# schematic.net
KiCad netlist of a schematic drawn in EasyEDA
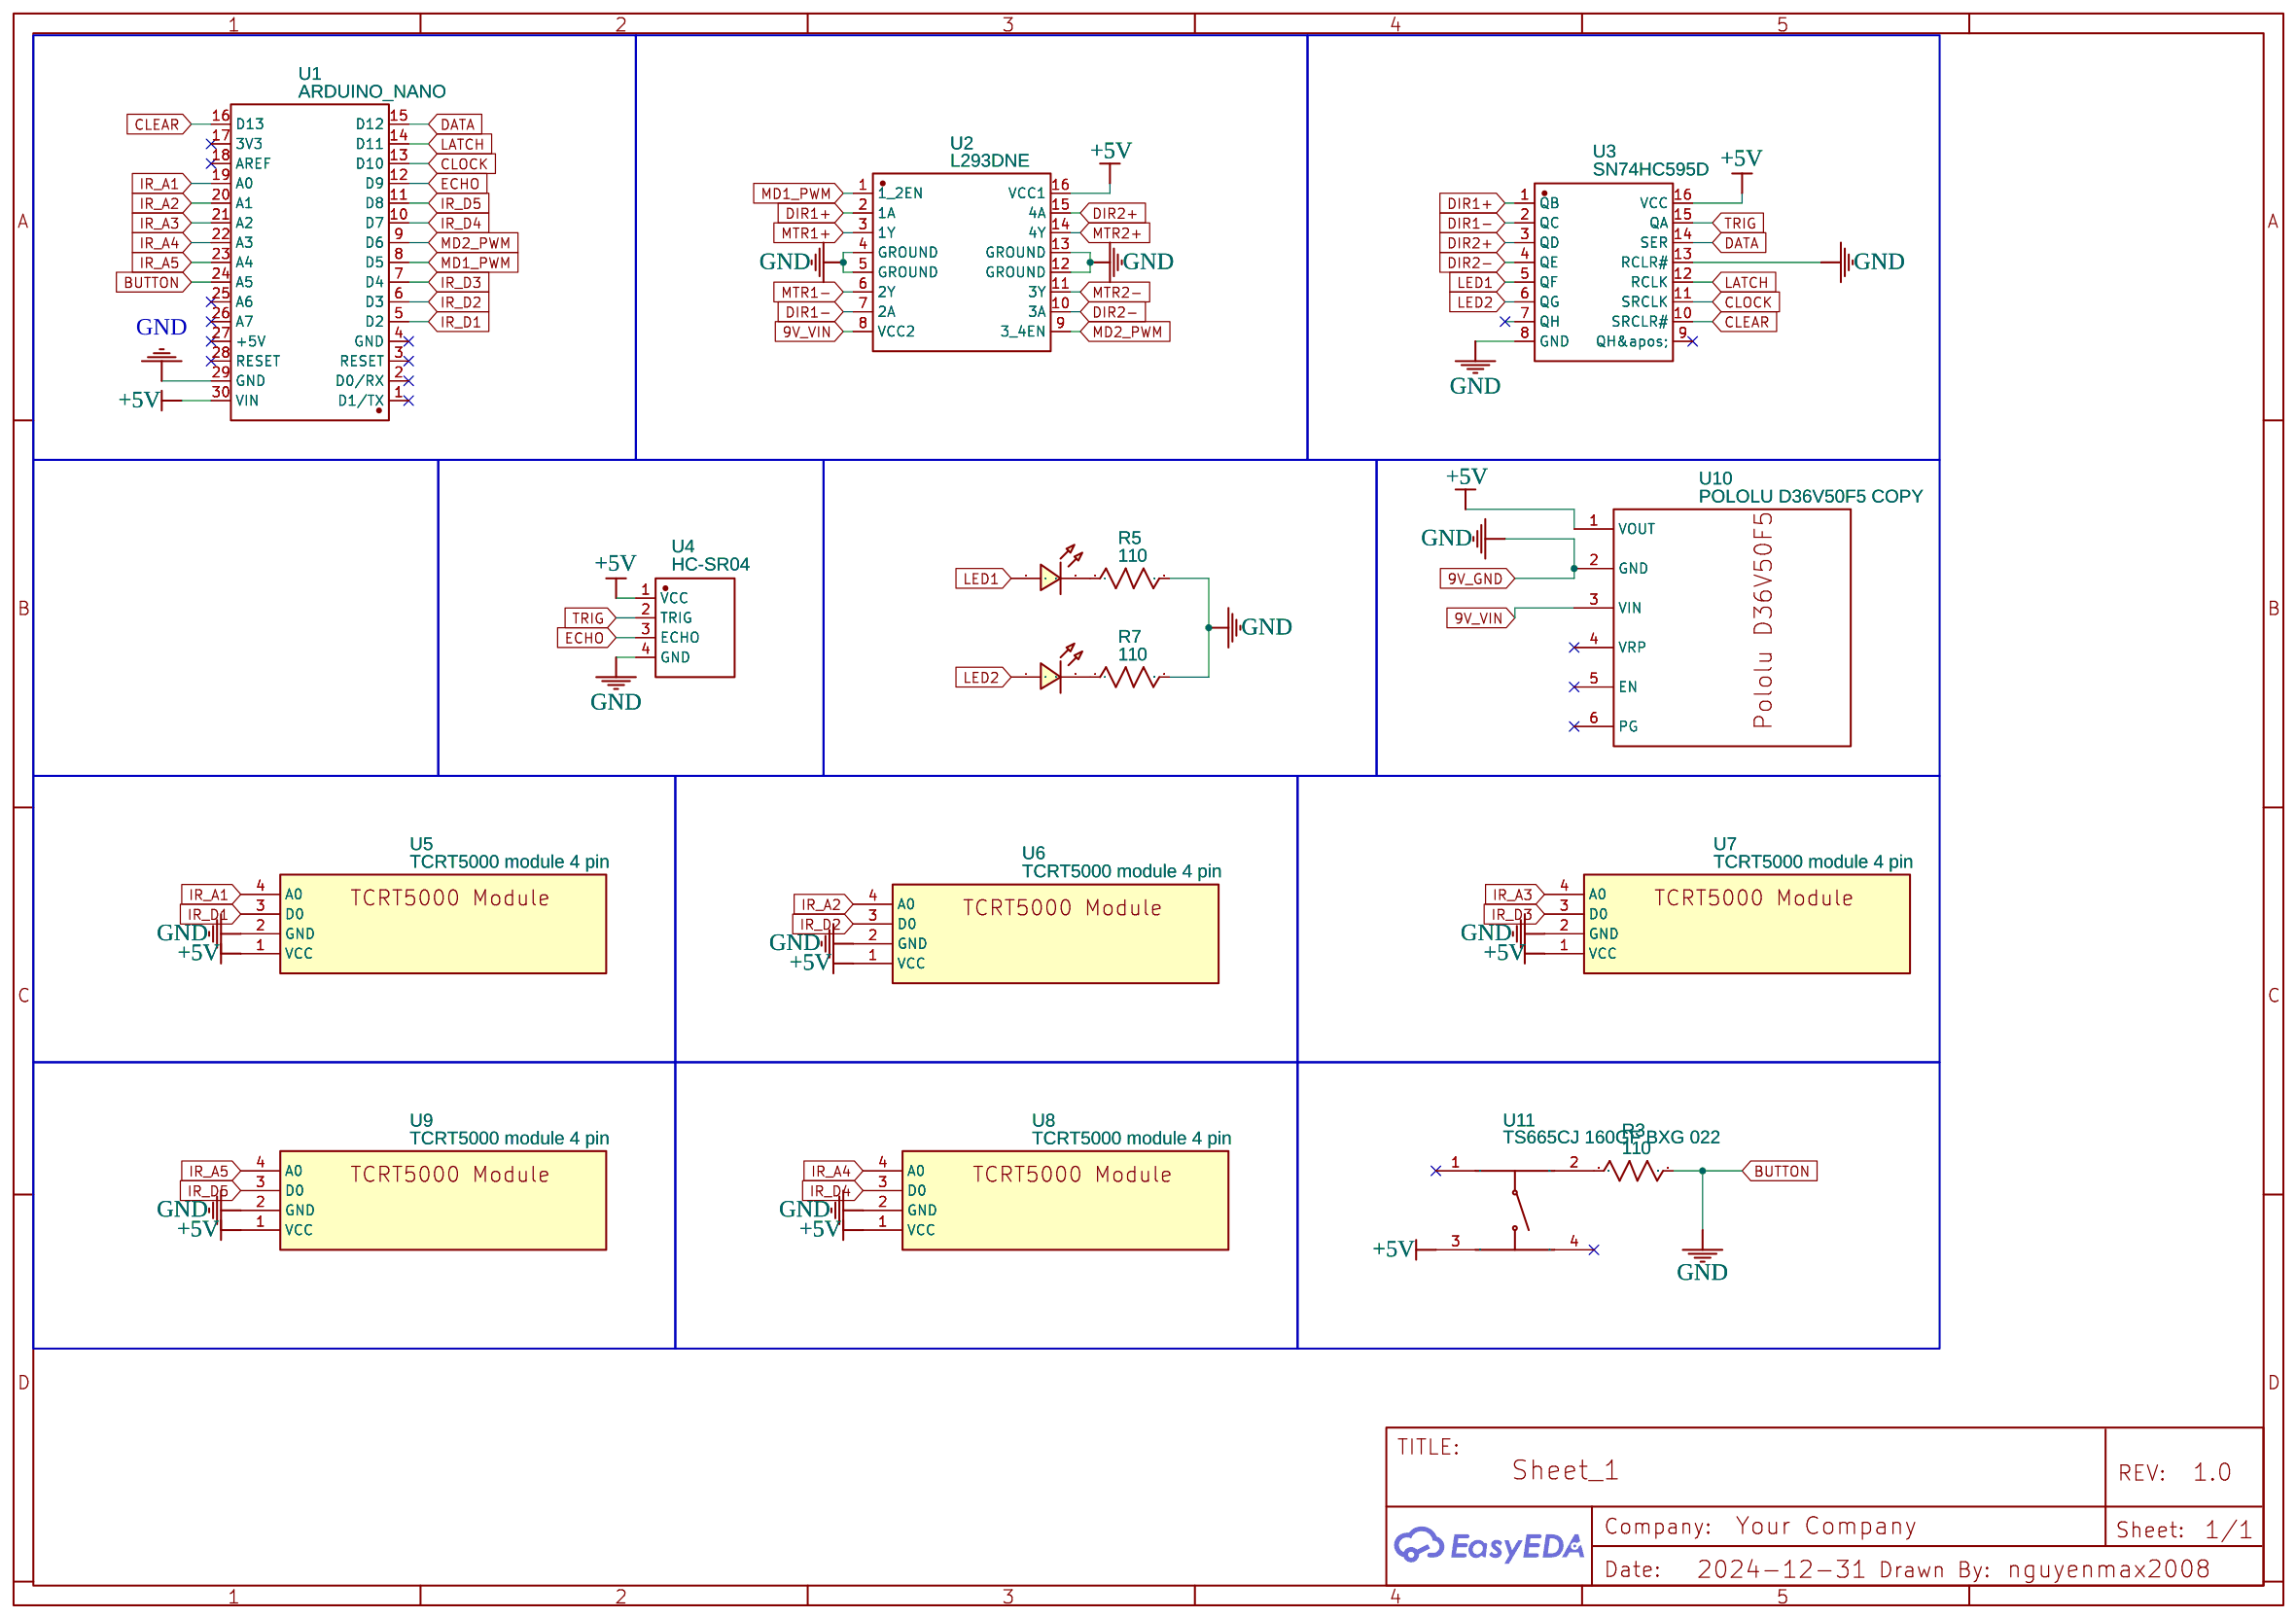
[diagram p0: schematic sheet]

(export (version "E")
  (design (tool "Eeschema 10.0.6"))
  (components
    (comp (ref "LED6")
      (value "LED-TH-3mm_R")
      (fields
        (field (name "Manufacturer Part") "204-10SDRD/S530-A3-L")
        (field (name "Manufacturer") "EVERLIGHT(台湾亿光)")
      )
      (libsource (lib "") (part "LED-TH-3mm_R"))
    )
    (comp (ref "LED9")
      (value "LED-TH-3mm_B")
      (fields
        (field (name "Manufacturer Part") "204-10SUBC/S400-A4")
        (field (name "Manufacturer") "EVERLIGHT(台湾亿光)")
      )
      (libsource (lib "") (part "LED-TH-3mm_B"))
    )
    (comp (ref "R3") (value "110") (libsource (lib "") (part "R_AXIAL-0.3_US")))
    (comp (ref "R5") (value "110") (libsource (lib "") (part "R_AXIAL-0.3_US")))
    (comp (ref "R7") (value "110") (libsource (lib "") (part "R_AXIAL-0.3_US")))
    (comp (ref "U1") (value "ARDUINO_NANO") (libsource (lib "") (part "ARDUINO_NANO")))
    (comp (ref "U2")
      (value "L293DNE")
      (fields (field (name "Manufacturer") "TI(德州仪器)"))
      (libsource (lib "") (part "L293DNE"))
    )
    (comp (ref "U3") (value "SN74HC595D") (libsource (lib "") (part "SN74HC595D")))
    (comp (ref "U4")
      (value "HC-SR04")
      (fields (field (name "Manufacturer") "Universal Microelectronics"))
      (libsource (lib "") (part "HC-SR04"))
    )
    (comp (ref "U5") (value "TCRT5000 module 4 pin") (libsource (lib "") (part "TCRT5000 module 4 pin")))
    (comp (ref "U6") (value "TCRT5000 module 4 pin") (libsource (lib "") (part "TCRT5000 module 4 pin")))
    (comp (ref "U7") (value "TCRT5000 module 4 pin") (libsource (lib "") (part "TCRT5000 module 4 pin")))
    (comp (ref "U8") (value "TCRT5000 module 4 pin") (libsource (lib "") (part "TCRT5000 module 4 pin")))
    (comp (ref "U9") (value "TCRT5000 module 4 pin") (libsource (lib "") (part "TCRT5000 module 4 pin")))
    (comp (ref "U10") (value "POLOLU D36V50F5 COPY") (libsource (lib "") (part "POLOLU D36V50F5 COPY")))
    (comp (ref "U11")
      (value "TS665CJ 160GF BXG 022")
      (fields
        (field (name "Manufacturer Part") "TS665CJ 160gf BXG 022")
        (field (name "Manufacturer") "SHOU HAN(首韩)")
      )
      (libsource (lib "") (part "TS665CJ 160GF BXG 022"))
    )
  )
  (nets
    (net (code "1") (name "+5V") (class "Default")
      (node (ref "U1") (pin "30") (pinfunction "VIN_30") (pintype "unspecified"))
      (node (ref "U10") (pin "1") (pinfunction "VOUT_1") (pintype "unspecified"))
      (node (ref "U11") (pin "3") (pinfunction "C_3") (pintype "unspecified"))
      (node (ref "U2") (pin "16") (pinfunction "VCC1_16") (pintype "unspecified"))
      (node (ref "U3") (pin "16") (pinfunction "VCC_16") (pintype "unspecified"))
      (node (ref "U4") (pin "1") (pinfunction "VCC_1") (pintype "unspecified"))
      (node (ref "U5") (pin "1") (pinfunction "VCC_1") (pintype "unspecified"))
      (node (ref "U6") (pin "1") (pinfunction "VCC_1") (pintype "unspecified"))
      (node (ref "U7") (pin "1") (pinfunction "VCC_1") (pintype "unspecified"))
      (node (ref "U8") (pin "1") (pinfunction "VCC_1") (pintype "unspecified"))
      (node (ref "U9") (pin "1") (pinfunction "VCC_1") (pintype "unspecified"))
    )
    (net (code "2") (name "9V_GND") (class "Default")
      (node (ref "R3") (pin "2") (pinfunction "2_2") (pintype "unspecified"))
      (node (ref "R5") (pin "2") (pinfunction "2_2") (pintype "unspecified"))
      (node (ref "R7") (pin "2") (pinfunction "2_2") (pintype "unspecified"))
      (node (ref "U1") (pin "24") (pinfunction "A5_24") (pintype "unspecified"))
      (node (ref "U1") (pin "29") (pinfunction "GND_29") (pintype "unspecified"))
      (node (ref "U10") (pin "2") (pinfunction "GND_2") (pintype "unspecified"))
      (node (ref "U2") (pin "12") (pinfunction "GROUND_12") (pintype "unspecified"))
      (node (ref "U2") (pin "13") (pinfunction "GROUND_13") (pintype "unspecified"))
      (node (ref "U2") (pin "4") (pinfunction "GROUND_4") (pintype "unspecified"))
      (node (ref "U2") (pin "5") (pinfunction "GROUND_5") (pintype "unspecified"))
      (node (ref "U3") (pin "13") (pinfunction "RCLR#_13") (pintype "unspecified"))
      (node (ref "U3") (pin "8") (pinfunction "GND_8") (pintype "unspecified"))
      (node (ref "U4") (pin "4") (pinfunction "GND_4") (pintype "unspecified"))
      (node (ref "U5") (pin "2") (pinfunction "GND_2") (pintype "unspecified"))
      (node (ref "U6") (pin "2") (pinfunction "GND_2") (pintype "unspecified"))
      (node (ref "U7") (pin "2") (pinfunction "GND_2") (pintype "unspecified"))
      (node (ref "U8") (pin "2") (pinfunction "GND_2") (pintype "unspecified"))
      (node (ref "U9") (pin "2") (pinfunction "GND_2") (pintype "unspecified"))
    )
    (net (code "3") (name "9V_VIN") (class "Default")
      (node (ref "U10") (pin "3") (pinfunction "VIN_3") (pintype "unspecified"))
      (node (ref "U2") (pin "8") (pinfunction "VCC2_8") (pintype "unspecified"))
    )
    (net (code "4") (name "CLEAR") (class "Default")
      (node (ref "U1") (pin "16") (pinfunction "D13_16") (pintype "unspecified"))
      (node (ref "U3") (pin "10") (pinfunction "SRCLR#_10") (pintype "unspecified"))
    )
    (net (code "5") (name "CLOCK") (class "Default")
      (node (ref "U1") (pin "13") (pinfunction "D10_13") (pintype "unspecified"))
      (node (ref "U3") (pin "11") (pinfunction "SRCLK_11") (pintype "unspecified"))
    )
    (net (code "6") (name "DATA") (class "Default")
      (node (ref "U1") (pin "15") (pinfunction "D12_15") (pintype "unspecified"))
      (node (ref "U3") (pin "14") (pinfunction "SER_14") (pintype "unspecified"))
    )
    (net (code "7") (name "DIR1+") (class "Default")
      (node (ref "U2") (pin "2") (pinfunction "1A_2") (pintype "unspecified"))
      (node (ref "U3") (pin "1") (pinfunction "QB_1") (pintype "unspecified"))
    )
    (net (code "8") (name "DIR1-") (class "Default")
      (node (ref "U2") (pin "7") (pinfunction "2A_7") (pintype "unspecified"))
      (node (ref "U3") (pin "2") (pinfunction "QC_2") (pintype "unspecified"))
    )
    (net (code "9") (name "DIR2+") (class "Default")
      (node (ref "U2") (pin "15") (pinfunction "4A_15") (pintype "unspecified"))
      (node (ref "U3") (pin "3") (pinfunction "QD_3") (pintype "unspecified"))
    )
    (net (code "10") (name "DIR2-") (class "Default")
      (node (ref "U2") (pin "10") (pinfunction "3A_10") (pintype "unspecified"))
      (node (ref "U3") (pin "4") (pinfunction "QE_4") (pintype "unspecified"))
    )
    (net (code "11") (name "ECHO") (class "Default")
      (node (ref "U1") (pin "12") (pinfunction "D9_12") (pintype "unspecified"))
      (node (ref "U4") (pin "3") (pinfunction "ECHO_3") (pintype "unspecified"))
    )
    (net (code "12") (name "IR_A1") (class "Default")
      (node (ref "U1") (pin "19") (pinfunction "A0_19") (pintype "unspecified"))
      (node (ref "U5") (pin "4") (pinfunction "A0_4") (pintype "unspecified"))
    )
    (net (code "13") (name "IR_A2") (class "Default")
      (node (ref "U1") (pin "20") (pinfunction "A1_20") (pintype "unspecified"))
      (node (ref "U6") (pin "4") (pinfunction "A0_4") (pintype "unspecified"))
    )
    (net (code "14") (name "IR_A3") (class "Default")
      (node (ref "U1") (pin "21") (pinfunction "A2_21") (pintype "unspecified"))
      (node (ref "U7") (pin "4") (pinfunction "A0_4") (pintype "unspecified"))
    )
    (net (code "15") (name "IR_A4") (class "Default")
      (node (ref "U1") (pin "22") (pinfunction "A3_22") (pintype "unspecified"))
      (node (ref "U8") (pin "4") (pinfunction "A0_4") (pintype "unspecified"))
    )
    (net (code "16") (name "IR_A5") (class "Default")
      (node (ref "U1") (pin "23") (pinfunction "A4_23") (pintype "unspecified"))
      (node (ref "U9") (pin "4") (pinfunction "A0_4") (pintype "unspecified"))
    )
    (net (code "17") (name "IR_D1") (class "Default")
      (node (ref "U1") (pin "5") (pinfunction "D2_5") (pintype "unspecified"))
      (node (ref "U5") (pin "3") (pinfunction "D0_3") (pintype "unspecified"))
    )
    (net (code "18") (name "IR_D2") (class "Default")
      (node (ref "U1") (pin "6") (pinfunction "D3_6") (pintype "unspecified"))
      (node (ref "U6") (pin "3") (pinfunction "D0_3") (pintype "unspecified"))
    )
    (net (code "19") (name "IR_D3") (class "Default")
      (node (ref "U1") (pin "7") (pinfunction "D4_7") (pintype "unspecified"))
      (node (ref "U7") (pin "3") (pinfunction "D0_3") (pintype "unspecified"))
    )
    (net (code "20") (name "IR_D4") (class "Default")
      (node (ref "U1") (pin "10") (pinfunction "D7_10") (pintype "unspecified"))
      (node (ref "U8") (pin "3") (pinfunction "D0_3") (pintype "unspecified"))
    )
    (net (code "21") (name "IR_D5") (class "Default")
      (node (ref "U1") (pin "11") (pinfunction "D8_11") (pintype "unspecified"))
      (node (ref "U9") (pin "3") (pinfunction "D0_3") (pintype "unspecified"))
    )
    (net (code "22") (name "LATCH") (class "Default")
      (node (ref "U1") (pin "14") (pinfunction "D11_14") (pintype "unspecified"))
      (node (ref "U3") (pin "12") (pinfunction "RCLK_12") (pintype "unspecified"))
    )
    (net (code "23") (name "LED1") (class "Default")
      (node (ref "LED6") (pin "1") (pinfunction "1_1") (pintype "unspecified"))
      (node (ref "U3") (pin "5") (pinfunction "QF_5") (pintype "unspecified"))
    )
    (net (code "24") (name "LED2") (class "Default")
      (node (ref "LED9") (pin "1") (pinfunction "1_1") (pintype "unspecified"))
      (node (ref "U3") (pin "6") (pinfunction "QG_6") (pintype "unspecified"))
    )
    (net (code "25") (name "MD1_PWM") (class "Default")
      (node (ref "U1") (pin "8") (pinfunction "D5_8") (pintype "unspecified"))
      (node (ref "U2") (pin "1") (pinfunction "1_2EN_1") (pintype "unspecified"))
    )
    (net (code "26") (name "MD2_PWM") (class "Default")
      (node (ref "U1") (pin "9") (pinfunction "D6_9") (pintype "unspecified"))
      (node (ref "U2") (pin "9") (pinfunction "3_4EN_9") (pintype "unspecified"))
    )
    (net (code "27") (name "MTR1+") (class "Default")
      (node (ref "U2") (pin "3") (pinfunction "1Y_3") (pintype "unspecified"))
    )
    (net (code "28") (name "MTR1-") (class "Default")
      (node (ref "U2") (pin "6") (pinfunction "2Y_6") (pintype "unspecified"))
    )
    (net (code "29") (name "MTR2+") (class "Default")
      (node (ref "U2") (pin "14") (pinfunction "4Y_14") (pintype "unspecified"))
    )
    (net (code "30") (name "MTR2-") (class "Default")
      (node (ref "U2") (pin "11") (pinfunction "3Y_11") (pintype "unspecified"))
    )
    (net (code "31") (name "Net-(LED6-Pad2)") (class "Default")
      (node (ref "LED6") (pin "2") (pinfunction "2_2") (pintype "unspecified"))
      (node (ref "R5") (pin "1") (pinfunction "1_1") (pintype "unspecified"))
    )
    (net (code "32") (name "Net-(LED9-Pad2)") (class "Default")
      (node (ref "LED9") (pin "2") (pinfunction "2_2") (pintype "unspecified"))
      (node (ref "R7") (pin "1") (pinfunction "1_1") (pintype "unspecified"))
    )
    (net (code "33") (name "Net-(U11-B)") (class "Default")
      (node (ref "R3") (pin "1") (pinfunction "1_1") (pintype "unspecified"))
      (node (ref "U11") (pin "2") (pinfunction "B_2") (pintype "unspecified"))
    )
    (net (code "34") (name "TRIG") (class "Default")
      (node (ref "U3") (pin "15") (pinfunction "QA_15") (pintype "unspecified"))
      (node (ref "U4") (pin "2") (pinfunction "TRIG_2") (pintype "unspecified"))
    )
    (net (code "35") (name "unconnected-(U1-+5V-Pad27)") (class "Default")
      (node (ref "U1") (pin "27") (pinfunction "+5V_27") (pintype "unspecified+no_connect"))
    )
    (net (code "36") (name "unconnected-(U1-3V3-Pad17)") (class "Default")
      (node (ref "U1") (pin "17") (pinfunction "3V3_17") (pintype "unspecified+no_connect"))
    )
    (net (code "37") (name "unconnected-(U1-A6-Pad25)") (class "Default")
      (node (ref "U1") (pin "25") (pinfunction "A6_25") (pintype "unspecified+no_connect"))
    )
    (net (code "38") (name "unconnected-(U1-A7-Pad26)") (class "Default")
      (node (ref "U1") (pin "26") (pinfunction "A7_26") (pintype "unspecified+no_connect"))
    )
    (net (code "39") (name "unconnected-(U1-AREF-Pad18)") (class "Default")
      (node (ref "U1") (pin "18") (pinfunction "AREF_18") (pintype "unspecified+no_connect"))
    )
    (net (code "40") (name "unconnected-(U1-D0{slash}RX-Pad2)") (class "Default")
      (node (ref "U1") (pin "2") (pinfunction "D0/RX_2") (pintype "unspecified+no_connect"))
    )
    (net (code "41") (name "unconnected-(U1-D1{slash}TX-Pad1)") (class "Default")
      (node (ref "U1") (pin "1") (pinfunction "D1/TX_1") (pintype "unspecified+no_connect"))
    )
    (net (code "42") (name "unconnected-(U1-GND-Pad4)") (class "Default")
      (node (ref "U1") (pin "4") (pinfunction "GND_4") (pintype "unspecified+no_connect"))
    )
    (net (code "43") (name "unconnected-(U1-RESET-Pad3)") (class "Default")
      (node (ref "U1") (pin "3") (pinfunction "RESET_3") (pintype "unspecified+no_connect"))
    )
    (net (code "44") (name "unconnected-(U1-RESET-Pad28)") (class "Default")
      (node (ref "U1") (pin "28") (pinfunction "RESET_28") (pintype "unspecified+no_connect"))
    )
    (net (code "45") (name "unconnected-(U3-QH&apos;-Pad9)") (class "Default")
      (node (ref "U3") (pin "9") (pinfunction "QH&apos;_9") (pintype "unspecified+no_connect"))
    )
    (net (code "46") (name "unconnected-(U3-QH-Pad7)") (class "Default")
      (node (ref "U3") (pin "7") (pinfunction "QH_7") (pintype "unspecified+no_connect"))
    )
    (net (code "47") (name "unconnected-(U10-EN-Pad5)") (class "Default")
      (node (ref "U10") (pin "5") (pinfunction "EN_5") (pintype "unspecified+no_connect"))
    )
    (net (code "48") (name "unconnected-(U10-PG-Pad6)") (class "Default")
      (node (ref "U10") (pin "6") (pinfunction "PG_6") (pintype "unspecified+no_connect"))
    )
    (net (code "49") (name "unconnected-(U10-VRP-Pad4)") (class "Default")
      (node (ref "U10") (pin "4") (pinfunction "VRP_4") (pintype "unspecified+no_connect"))
    )
    (net (code "50") (name "unconnected-(U11-A-Pad1)") (class "Default")
      (node (ref "U11") (pin "1") (pinfunction "A_1") (pintype "unspecified+no_connect"))
    )
    (net (code "51") (name "unconnected-(U11-D-Pad4)") (class "Default")
      (node (ref "U11") (pin "4") (pinfunction "D_4") (pintype "unspecified+no_connect"))
    )
  )
)
